# Buck_3V3_D20V10F3.net
KiCad netlist of a schematic drawn in EAGLE
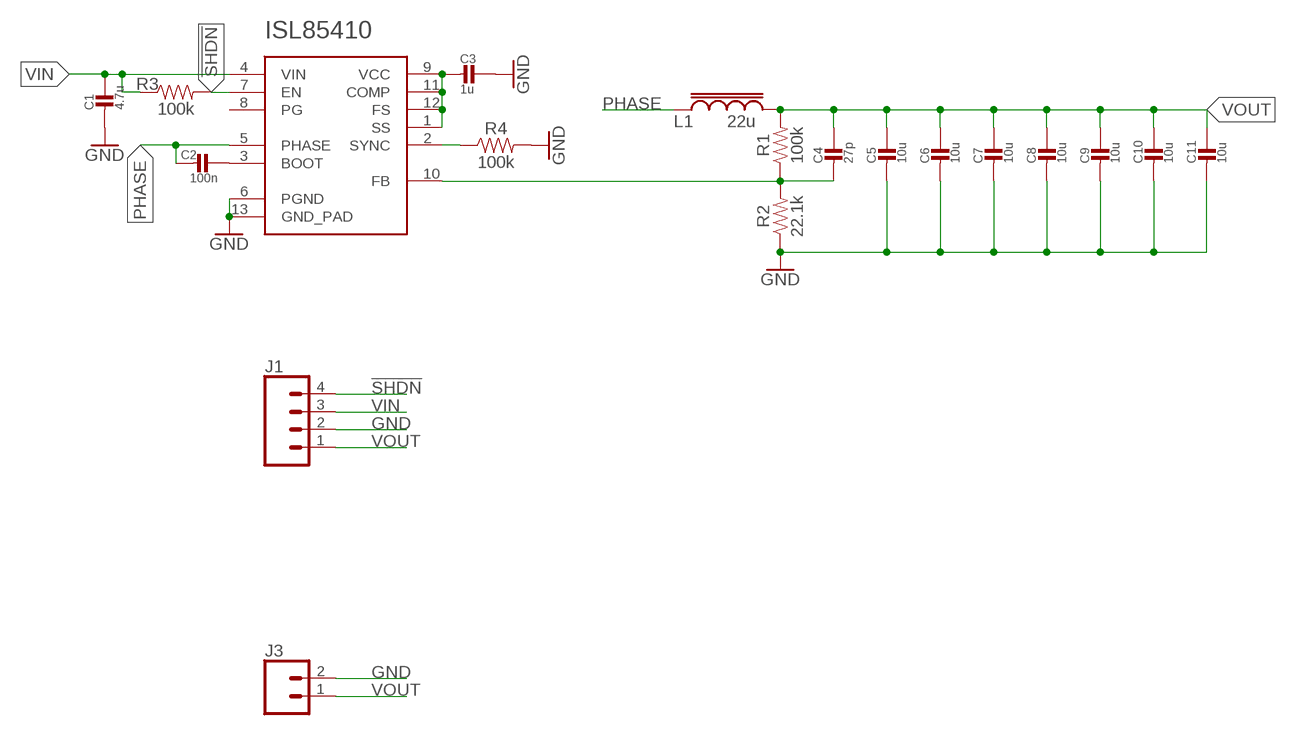
[diagram p0: schematic, sheet 1]

(export (version "E")
  (design (tool "Eeschema 10.0.6"))
  (components
    (comp (ref "C1")
      (value "4.7u")
      (footprint "eagle-import:0603")
      (libsource (lib "eagle-import") (part "CAP_CERAMIC_0603"))
    )
    (comp (ref "C2")
      (value "100n")
      (footprint "eagle-import:0603")
      (libsource (lib "eagle-import") (part "CAP_CERAMIC_0603"))
    )
    (comp (ref "C3")
      (value "1u")
      (footprint "eagle-import:0603")
      (libsource (lib "eagle-import") (part "CAP_CERAMIC_0603"))
    )
    (comp (ref "C4")
      (value "27p")
      (footprint "eagle-import:0603")
      (libsource (lib "eagle-import") (part "CAP_CERAMIC_0603"))
    )
    (comp (ref "C5")
      (value "10u")
      (footprint "eagle-import:0805")
      (libsource (lib "eagle-import") (part "CAP_CERAMIC_0805"))
    )
    (comp (ref "C6")
      (value "10u")
      (footprint "eagle-import:0805")
      (libsource (lib "eagle-import") (part "CAP_CERAMIC_0805"))
    )
    (comp (ref "C7")
      (value "10u")
      (footprint "eagle-import:0805")
      (libsource (lib "eagle-import") (part "CAP_CERAMIC_0805"))
    )
    (comp (ref "C8")
      (value "10u")
      (footprint "eagle-import:0805")
      (libsource (lib "eagle-import") (part "CAP_CERAMIC_0805"))
    )
    (comp (ref "C9")
      (value "10u")
      (footprint "eagle-import:0805")
      (libsource (lib "eagle-import") (part "CAP_CERAMIC_0805"))
    )
    (comp (ref "C10")
      (value "10u")
      (footprint "eagle-import:0805")
      (libsource (lib "eagle-import") (part "CAP_CERAMIC_0805"))
    )
    (comp (ref "C11")
      (value "10u")
      (footprint "eagle-import:0805")
      (libsource (lib "eagle-import") (part "CAP_CERAMIC_0805"))
    )
    (comp (ref "ISL85410")
      (value "BUCK_ISL85410")
      (footprint "eagle-import:DFN-12_DE-L")
      (libsource (lib "eagle-import") (part "BUCK_ISL85410"))
    )
    (comp (ref "J1")
      (value "CONN_041X04_NO_SILK")
      (footprint "eagle-import:1X04_NO_SILK")
      (libsource (lib "eagle-import") (part "CONN_041X04_NO_SILK"))
    )
    (comp (ref "J3")
      (value "CONN_021X02_NO_SILK")
      (footprint "eagle-import:1X02_NO_SILK")
      (libsource (lib "eagle-import") (part "CONN_021X02_NO_SILK"))
    )
    (comp (ref "L1")
      (value "22u")
      (footprint "eagle-import:CD54")
      (libsource (lib "eagle-import") (part "INDUCTOR-CD54"))
    )
    (comp (ref "R1")
      (value "100k")
      (footprint "eagle-import:0603")
      (libsource (lib "eagle-import") (part "RESISTOR0603"))
    )
    (comp (ref "R2")
      (value "22.1k")
      (footprint "eagle-import:0603")
      (libsource (lib "eagle-import") (part "RESISTOR0603"))
    )
    (comp (ref "R3")
      (value "100k")
      (footprint "eagle-import:0603")
      (libsource (lib "eagle-import") (part "RESISTOR0603"))
    )
    (comp (ref "R4")
      (value "100k")
      (footprint "eagle-import:0603")
      (libsource (lib "eagle-import") (part "RESISTOR0603"))
    )
  )
  (nets
    (net (code "1") (name "/~{SHDN}") (class "Default")
      (node (ref "ISL85410") (pin "7") (pinfunction "EN_7") (pintype "bidirectional"))
      (node (ref "J1") (pin "4") (pinfunction "4_4") (pintype "passive"))
      (node (ref "R3") (pin "2") (pinfunction "2_2") (pintype "passive"))
    )
    (net (code "2") (name "Net-(ISL85410-BOOT)") (class "Default")
      (node (ref "C2") (pin "1") (pinfunction "1_1") (pintype "passive"))
      (node (ref "ISL85410") (pin "3") (pinfunction "BOOT_3") (pintype "bidirectional"))
    )
    (net (code "3") (name "Net-(ISL85410-COMP)") (class "Default")
      (node (ref "C3") (pin "2") (pinfunction "2_2") (pintype "passive"))
      (node (ref "ISL85410") (pin "1") (pinfunction "SS_1") (pintype "bidirectional"))
      (node (ref "ISL85410") (pin "11") (pinfunction "COMP_11") (pintype "bidirectional"))
      (node (ref "ISL85410") (pin "12") (pinfunction "FS_12") (pintype "bidirectional"))
      (node (ref "ISL85410") (pin "9") (pinfunction "VCC_9") (pintype "bidirectional"))
    )
    (net (code "4") (name "Net-(ISL85410-FB)") (class "Default")
      (node (ref "C4") (pin "2") (pinfunction "2_2") (pintype "passive"))
      (node (ref "ISL85410") (pin "10") (pinfunction "FB_10") (pintype "bidirectional"))
      (node (ref "R1") (pin "1") (pinfunction "1_1") (pintype "passive"))
      (node (ref "R2") (pin "2") (pinfunction "2_2") (pintype "passive"))
    )
    (net (code "5") (name "Net-(ISL85410-SYNC)") (class "Default")
      (node (ref "ISL85410") (pin "2") (pinfunction "SYNC_2") (pintype "bidirectional"))
      (node (ref "R4") (pin "1") (pinfunction "1_1") (pintype "passive"))
    )
    (net (code "6") (name "PHASE") (class "Default")
      (node (ref "C2") (pin "2") (pinfunction "2_2") (pintype "passive"))
      (node (ref "ISL85410") (pin "5") (pinfunction "PHASE_5") (pintype "bidirectional"))
      (node (ref "L1") (pin "P$1") (pinfunction "P$1_P$1") (pintype "passive"))
    )
    (net (code "7") (name "SUPPLY_GND") (class "Default")
      (node (ref "C1") (pin "2") (pinfunction "2_2") (pintype "passive"))
      (node (ref "C10") (pin "2") (pinfunction "2_2") (pintype "passive"))
      (node (ref "C11") (pin "2") (pinfunction "2_2") (pintype "passive"))
      (node (ref "C3") (pin "1") (pinfunction "1_1") (pintype "passive"))
      (node (ref "C5") (pin "2") (pinfunction "2_2") (pintype "passive"))
      (node (ref "C6") (pin "2") (pinfunction "2_2") (pintype "passive"))
      (node (ref "C7") (pin "2") (pinfunction "2_2") (pintype "passive"))
      (node (ref "C8") (pin "2") (pinfunction "2_2") (pintype "passive"))
      (node (ref "C9") (pin "2") (pinfunction "2_2") (pintype "passive"))
      (node (ref "ISL85410") (pin "13") (pinfunction "GND_PAD_13") (pintype "bidirectional"))
      (node (ref "ISL85410") (pin "6") (pinfunction "PGND_6") (pintype "bidirectional"))
      (node (ref "J1") (pin "2") (pinfunction "2_2") (pintype "passive"))
      (node (ref "J3") (pin "2") (pinfunction "2_2") (pintype "passive"))
      (node (ref "R2") (pin "1") (pinfunction "1_1") (pintype "passive"))
      (node (ref "R4") (pin "2") (pinfunction "2_2") (pintype "passive"))
    )
    (net (code "8") (name "VIN") (class "Default")
      (node (ref "C1") (pin "1") (pinfunction "1_1") (pintype "passive"))
      (node (ref "ISL85410") (pin "4") (pinfunction "VIN_4") (pintype "bidirectional"))
      (node (ref "J1") (pin "3") (pinfunction "3_3") (pintype "passive"))
      (node (ref "R3") (pin "1") (pinfunction "1_1") (pintype "passive"))
    )
    (net (code "9") (name "VOUT") (class "Default")
      (node (ref "C10") (pin "1") (pinfunction "1_1") (pintype "passive"))
      (node (ref "C11") (pin "1") (pinfunction "1_1") (pintype "passive"))
      (node (ref "C4") (pin "1") (pinfunction "1_1") (pintype "passive"))
      (node (ref "C5") (pin "1") (pinfunction "1_1") (pintype "passive"))
      (node (ref "C6") (pin "1") (pinfunction "1_1") (pintype "passive"))
      (node (ref "C7") (pin "1") (pinfunction "1_1") (pintype "passive"))
      (node (ref "C8") (pin "1") (pinfunction "1_1") (pintype "passive"))
      (node (ref "C9") (pin "1") (pinfunction "1_1") (pintype "passive"))
      (node (ref "J1") (pin "1") (pinfunction "1_1") (pintype "passive"))
      (node (ref "J3") (pin "1") (pinfunction "1_1") (pintype "passive"))
      (node (ref "L1") (pin "P$2") (pinfunction "P$2_P$2") (pintype "passive"))
      (node (ref "R1") (pin "2") (pinfunction "2_2") (pintype "passive"))
    )
    (net (code "10") (name "unconnected-(ISL85410-PG-Pad8)") (class "Default")
      (node (ref "ISL85410") (pin "8") (pinfunction "PG_8") (pintype "bidirectional"))
    )
  )
)
